# espi.net
KiCad netlist of a schematic drawn in EAGLE
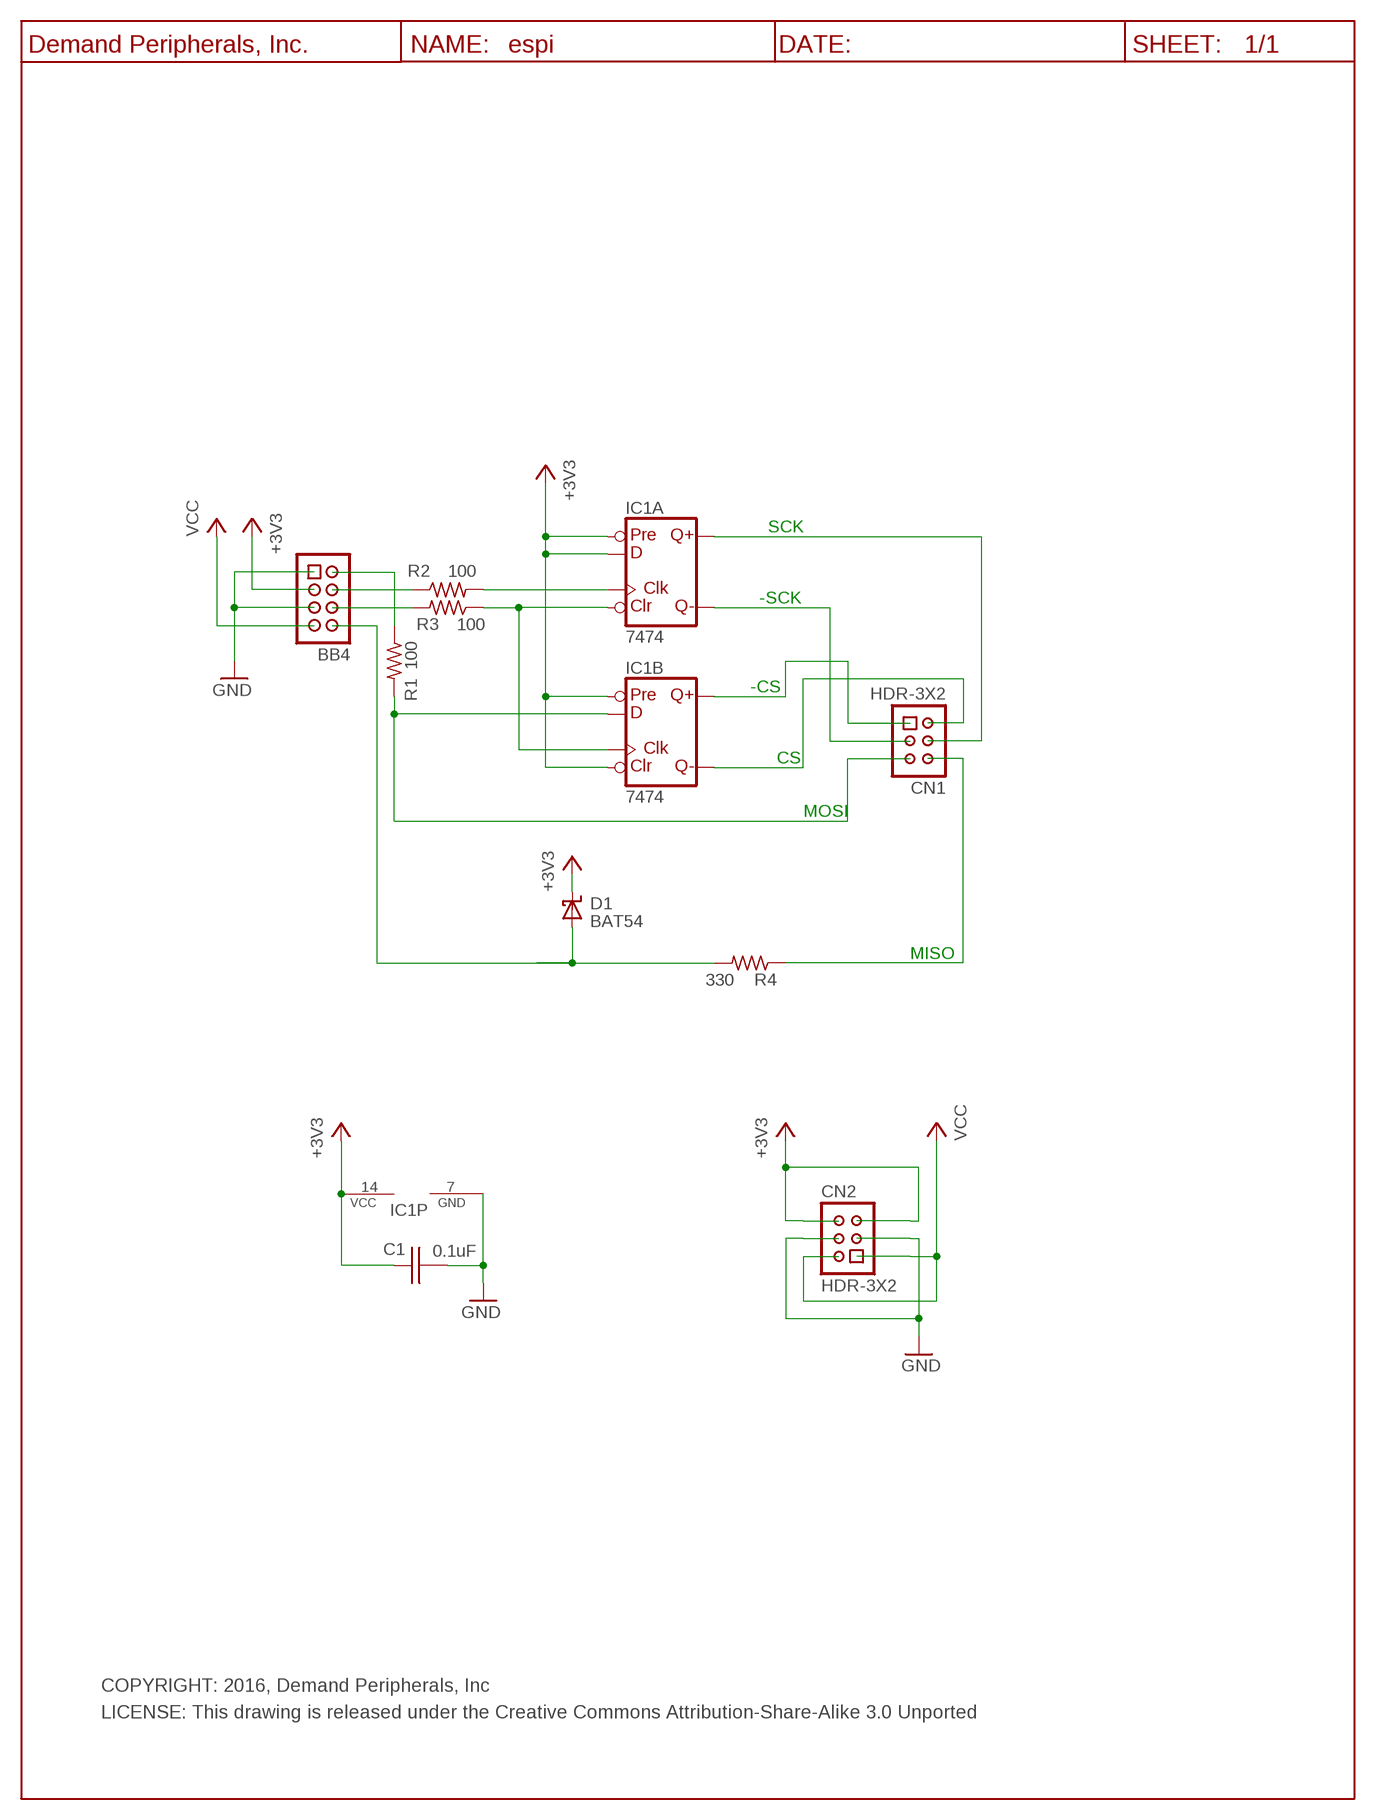
[diagram p0: schematic, sheet 1]

(export (version "E")
  (design (tool "Eeschema 10.0.6"))
  (components
    (comp (ref "BB4")
      (value "BB_CON")
      (footprint "eagle-import:HDR-4X2")
      (libsource (lib "eagle-import") (part "HDR-4X2-SHR"))
    )
    (comp (ref "C1")
      (value "0.1uF")
      (footprint "eagle-import:C0603")
      (libsource (lib "eagle-import") (part "C0.1UF_C0603"))
    )
    (comp (ref "CN1")
      (value "HDR-3X2")
      (footprint "eagle-import:HDR-3X2")
      (libsource (lib "eagle-import") (part "HDR-3X2"))
    )
    (comp (ref "CN2")
      (value "HDR-3X2")
      (footprint "eagle-import:HDR-3X2")
      (libsource (lib "eagle-import") (part "HDR-3X2"))
    )
    (comp (ref "D1")
      (value "BAT54")
      (footprint "eagle-import:SOT23")
      (libsource (lib "eagle-import") (part "BAT54"))
    )
    (comp (ref "IC1")
      (value "7474")
      (footprint "eagle-import:SO14")
      (libsource (lib "eagle-import") (part "74AHC74SS"))
    )
    (comp (ref "R1")
      (value "100")
      (footprint "eagle-import:R0603")
      (libsource (lib "eagle-import") (part "R100_R0603"))
    )
    (comp (ref "R2")
      (value "100")
      (footprint "eagle-import:R0603")
      (libsource (lib "eagle-import") (part "R100_R0603"))
    )
    (comp (ref "R3")
      (value "100")
      (footprint "eagle-import:R0603")
      (libsource (lib "eagle-import") (part "R100_R0603"))
    )
    (comp (ref "R4")
      (value "330")
      (footprint "eagle-import:R0603")
      (libsource (lib "eagle-import") (part "R330_R0603"))
    )
    (comp (ref "U$3")
      (value "DP_FRAME_P")
      (footprint "eagle-import:P_FRAME")
      (libsource (lib "eagle-import") (part "DP_FRAME_P"))
    )
  )
  (nets
    (net (code "1") (name "+3V3") (class "Default")
      (node (ref "BB4") (pin "3") (pinfunction "3_3") (pintype "passive"))
      (node (ref "C1") (pin "1") (pinfunction "1_1") (pintype "passive"))
      (node (ref "CN2") (pin "5") (pinfunction "5_5") (pintype "passive"))
      (node (ref "CN2") (pin "6") (pinfunction "6_6") (pintype "passive"))
      (node (ref "D1") (pin "3") (pinfunction "CC_3") (pintype "passive"))
      (node (ref "IC1") (pin "10") (pinfunction "PRE_10") (pintype "input"))
      (node (ref "IC1") (pin "13") (pinfunction "CLR_13") (pintype "input"))
      (node (ref "IC1") (pin "14") (pinfunction "VCC_14") (pintype "power_in"))
      (node (ref "IC1") (pin "2") (pinfunction "D_2") (pintype "input"))
      (node (ref "IC1") (pin "4") (pinfunction "PRE_4") (pintype "input"))
    )
    (net (code "2") (name "GND") (class "Default")
      (node (ref "BB4") (pin "1") (pinfunction "1_1") (pintype "passive"))
      (node (ref "BB4") (pin "5") (pinfunction "5_5") (pintype "passive"))
      (node (ref "C1") (pin "2") (pinfunction "2_2") (pintype "passive"))
      (node (ref "CN2") (pin "3") (pinfunction "3_3") (pintype "passive"))
      (node (ref "CN2") (pin "4") (pinfunction "4_4") (pintype "passive"))
      (node (ref "IC1") (pin "7") (pinfunction "GND_7") (pintype "power_in"))
    )
    (net (code "3") (name "Net-(BB4-Pad2)") (class "Default")
      (node (ref "BB4") (pin "2") (pinfunction "2_2") (pintype "passive"))
      (node (ref "R1") (pin "1") (pinfunction "1_1") (pintype "passive"))
    )
    (net (code "4") (name "Net-(BB4-Pad4)") (class "Default")
      (node (ref "BB4") (pin "4") (pinfunction "4_4") (pintype "passive"))
      (node (ref "R2") (pin "1") (pinfunction "1_1") (pintype "passive"))
    )
    (net (code "5") (name "Net-(BB4-Pad6)") (class "Default")
      (node (ref "BB4") (pin "6") (pinfunction "6_6") (pintype "passive"))
      (node (ref "R3") (pin "2") (pinfunction "2_2") (pintype "passive"))
    )
    (net (code "6") (name "Net-(CN1-Pad6)") (class "Default")
      (node (ref "CN1") (pin "6") (pinfunction "6_6") (pintype "passive"))
      (node (ref "R4") (pin "1") (pinfunction "1_1") (pintype "passive"))
    )
    (net (code "7") (name "Net-(D1-A)") (class "Default")
      (node (ref "BB4") (pin "8") (pinfunction "8_8") (pintype "passive"))
      (node (ref "D1") (pin "1") (pinfunction "A_1") (pintype "passive"))
      (node (ref "R4") (pin "2") (pinfunction "2_2") (pintype "passive"))
    )
    (net (code "8") (name "Net-(IC1A-CLK)") (class "Default")
      (node (ref "IC1") (pin "3") (pinfunction "CLK_3") (pintype "input"))
      (node (ref "R2") (pin "2") (pinfunction "2_2") (pintype "passive"))
    )
    (net (code "9") (name "Net-(IC1A-CLR)") (class "Default")
      (node (ref "IC1") (pin "1") (pinfunction "CLR_1") (pintype "input"))
      (node (ref "IC1") (pin "11") (pinfunction "CLK_11") (pintype "input"))
      (node (ref "R3") (pin "1") (pinfunction "1_1") (pintype "passive"))
    )
    (net (code "10") (name "Net-(IC1A-Q)") (class "Default")
      (node (ref "CN1") (pin "4") (pinfunction "4_4") (pintype "passive"))
      (node (ref "IC1") (pin "5") (pinfunction "Q_5") (pintype "output"))
    )
    (net (code "11") (name "Net-(IC1A-~{Q})") (class "Default")
      (node (ref "CN1") (pin "3") (pinfunction "3_3") (pintype "passive"))
      (node (ref "IC1") (pin "6") (pinfunction "~{Q}_6") (pintype "output"))
    )
    (net (code "12") (name "Net-(IC1B-D)") (class "Default")
      (node (ref "CN1") (pin "5") (pinfunction "5_5") (pintype "passive"))
      (node (ref "IC1") (pin "12") (pinfunction "D_12") (pintype "input"))
      (node (ref "R1") (pin "2") (pinfunction "2_2") (pintype "passive"))
    )
    (net (code "13") (name "Net-(IC1B-Q)") (class "Default")
      (node (ref "CN1") (pin "1") (pinfunction "1_1") (pintype "passive"))
      (node (ref "IC1") (pin "9") (pinfunction "Q_9") (pintype "output"))
    )
    (net (code "14") (name "Net-(IC1B-~{Q})") (class "Default")
      (node (ref "CN1") (pin "2") (pinfunction "2_2") (pintype "passive"))
      (node (ref "IC1") (pin "8") (pinfunction "~{Q}_8") (pintype "output"))
    )
    (net (code "15") (name "VCC") (class "Default")
      (node (ref "BB4") (pin "7") (pinfunction "7_7") (pintype "passive"))
      (node (ref "CN2") (pin "1") (pinfunction "1_1") (pintype "passive"))
      (node (ref "CN2") (pin "2") (pinfunction "2_2") (pintype "passive"))
    )
  )
)
